# MTX_pic_piggyback_V12.net
KiCad netlist of a schematic drawn in EAGLE
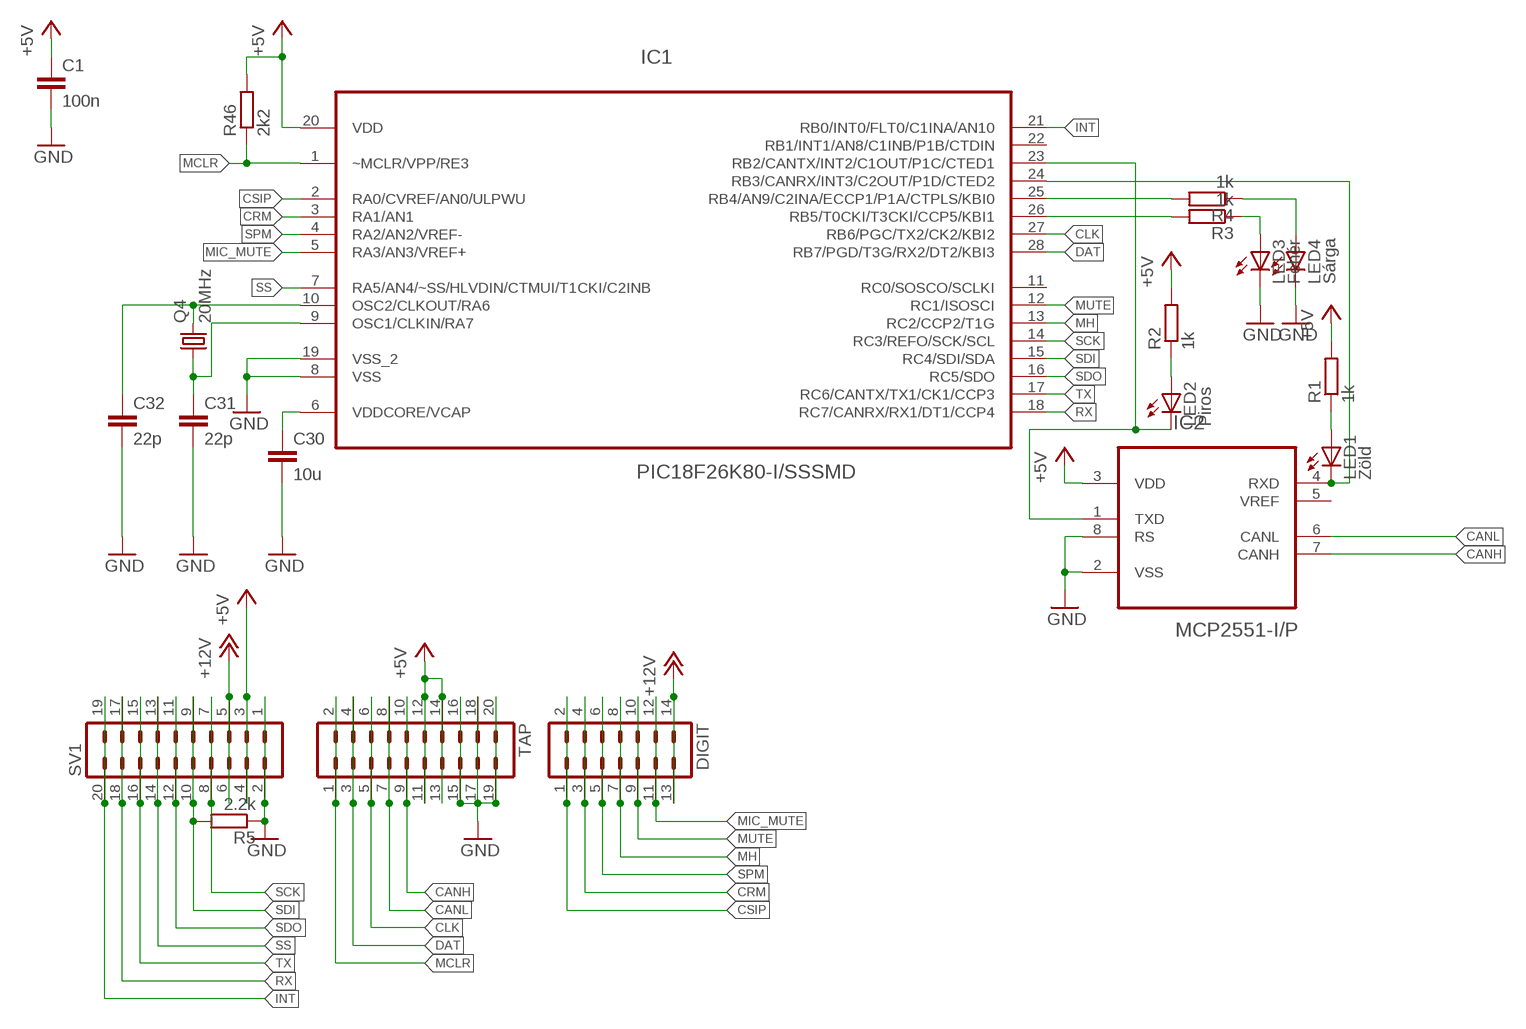
[diagram p0: schematic, sheet 1]

(export (version "E")
  (design (tool "Eeschema 10.0.6"))
  (components
    (comp (ref "C1")
      (value "100n")
      (footprint "eagle-import:C0805")
      (libsource (lib "eagle-import") (part "C-EUC0805"))
    )
    (comp (ref "C30")
      (value "10u")
      (footprint "eagle-import:C0805")
      (libsource (lib "eagle-import") (part "C-EUC0805"))
    )
    (comp (ref "C31")
      (value "22p")
      (footprint "eagle-import:C0805")
      (libsource (lib "eagle-import") (part "C-EUC0805"))
    )
    (comp (ref "C32")
      (value "22p")
      (footprint "eagle-import:C0805")
      (libsource (lib "eagle-import") (part "C-EUC0805"))
    )
    (comp (ref "DIGIT")
      (value "MA07-2")
      (footprint "eagle-import:MA07-2")
      (libsource (lib "eagle-import") (part "MA07-2"))
    )
    (comp (ref "IC1")
      (value "PIC18F26K80-I/SSSMD")
      (footprint "eagle-import:SOP65P780X200-28N")
      (libsource (lib "eagle-import") (part "PIC18F25K80-I/SSSMD"))
    )
    (comp (ref "IC2")
      (value "MCP2551-I/P")
      (footprint "eagle-import:DIP254P762X432-8")
      (libsource (lib "eagle-import") (part "MCP2551-I/P"))
    )
    (comp (ref "LED1")
      (value "Zöld")
      (footprint "eagle-import:CHIP-LED0805")
      (libsource (lib "eagle-import") (part "LEDCHIP-LED0805"))
    )
    (comp (ref "LED2")
      (value "Piros")
      (footprint "eagle-import:CHIP-LED0805")
      (libsource (lib "eagle-import") (part "LEDCHIP-LED0805"))
    )
    (comp (ref "LED3")
      (value "Fehér")
      (footprint "eagle-import:CHIP-LED0805")
      (libsource (lib "eagle-import") (part "LEDCHIP-LED0805"))
    )
    (comp (ref "LED4")
      (value "Sárga")
      (footprint "eagle-import:CHIP-LED0805")
      (libsource (lib "eagle-import") (part "LEDCHIP-LED0805"))
    )
    (comp (ref "Q4")
      (value "20MHz")
      (footprint "eagle-import:HC49UP")
      (libsource (lib "eagle-import") (part "CRYSTALHC49UP"))
    )
    (comp (ref "R1")
      (value "1k")
      (footprint "eagle-import:R0805")
      (libsource (lib "eagle-import") (part "R-EU_R0805"))
    )
    (comp (ref "R2")
      (value "1k")
      (footprint "eagle-import:R0805")
      (libsource (lib "eagle-import") (part "R-EU_R0805"))
    )
    (comp (ref "R3")
      (value "1k")
      (footprint "eagle-import:R0805")
      (libsource (lib "eagle-import") (part "R-EU_R0805"))
    )
    (comp (ref "R4")
      (value "1k")
      (footprint "eagle-import:R0805")
      (libsource (lib "eagle-import") (part "R-EU_R0805"))
    )
    (comp (ref "R5")
      (value "2.2k")
      (footprint "eagle-import:R0805")
      (libsource (lib "eagle-import") (part "R-EU_R0805"))
    )
    (comp (ref "R46")
      (value "2k2")
      (footprint "eagle-import:R0805")
      (libsource (lib "eagle-import") (part "R-EU_R0805"))
    )
    (comp (ref "SV1")
      (value "MA10-2")
      (footprint "eagle-import:MA10-2")
      (libsource (lib "eagle-import") (part "MA10-2"))
    )
    (comp (ref "TAP")
      (value "MA10-2")
      (footprint "eagle-import:MA10-2")
      (libsource (lib "eagle-import") (part "MA10-2"))
    )
  )
  (nets
    (net (code "1") (name "+5V") (class "Default")
      (node (ref "C1") (pin "1") (pinfunction "1_1") (pintype "passive"))
      (node (ref "IC1") (pin "20") (pinfunction "VDD_20") (pintype "power_in"))
      (node (ref "IC2") (pin "3") (pinfunction "VDD_3") (pintype "power_in"))
      (node (ref "R1") (pin "2") (pinfunction "2_2") (pintype "passive"))
      (node (ref "R2") (pin "2") (pinfunction "2_2") (pintype "passive"))
      (node (ref "R46") (pin "2") (pinfunction "2_2") (pintype "passive"))
      (node (ref "SV1") (pin "3") (pinfunction "3_3") (pintype "passive"))
      (node (ref "SV1") (pin "4") (pinfunction "4_4") (pintype "passive"))
      (node (ref "TAP") (pin "11") (pinfunction "11_11") (pintype "passive"))
      (node (ref "TAP") (pin "12") (pinfunction "12_12") (pintype "passive"))
      (node (ref "TAP") (pin "13") (pinfunction "13_13") (pintype "passive"))
      (node (ref "TAP") (pin "14") (pinfunction "14_14") (pintype "passive"))
    )
    (net (code "2") (name "+12V") (class "Default")
      (node (ref "DIGIT") (pin "13") (pinfunction "13_13") (pintype "passive"))
      (node (ref "DIGIT") (pin "14") (pinfunction "14_14") (pintype "passive"))
      (node (ref "SV1") (pin "5") (pinfunction "5_5") (pintype "passive"))
      (node (ref "SV1") (pin "6") (pinfunction "6_6") (pintype "passive"))
    )
    (net (code "3") (name "CANH") (class "Default")
      (node (ref "IC2") (pin "7") (pinfunction "CANH_7") (pintype "bidirectional"))
      (node (ref "TAP") (pin "10") (pinfunction "10_10") (pintype "passive"))
      (node (ref "TAP") (pin "9") (pinfunction "9_9") (pintype "passive"))
    )
    (net (code "4") (name "CANL") (class "Default")
      (node (ref "IC2") (pin "6") (pinfunction "CANL_6") (pintype "bidirectional"))
      (node (ref "TAP") (pin "7") (pinfunction "7_7") (pintype "passive"))
      (node (ref "TAP") (pin "8") (pinfunction "8_8") (pintype "passive"))
    )
    (net (code "5") (name "CLK") (class "Default")
      (node (ref "IC1") (pin "27") (pinfunction "RB6/PGC/TX2/CK2/KBI2_27") (pintype "bidirectional"))
      (node (ref "TAP") (pin "5") (pinfunction "5_5") (pintype "passive"))
      (node (ref "TAP") (pin "6") (pinfunction "6_6") (pintype "passive"))
    )
    (net (code "6") (name "CRM") (class "Default")
      (node (ref "DIGIT") (pin "3") (pinfunction "3_3") (pintype "passive"))
      (node (ref "DIGIT") (pin "4") (pinfunction "4_4") (pintype "passive"))
      (node (ref "IC1") (pin "3") (pinfunction "RA1/AN1_3") (pintype "bidirectional"))
    )
    (net (code "7") (name "CSIP") (class "Default")
      (node (ref "DIGIT") (pin "1") (pinfunction "1_1") (pintype "passive"))
      (node (ref "DIGIT") (pin "2") (pinfunction "2_2") (pintype "passive"))
      (node (ref "IC1") (pin "2") (pinfunction "RA0/CVREF/AN0/ULPWU_2") (pintype "bidirectional"))
    )
    (net (code "8") (name "DAT") (class "Default")
      (node (ref "IC1") (pin "28") (pinfunction "RB7/PGD/T3G/RX2/DT2/KBI3_28") (pintype "bidirectional"))
      (node (ref "TAP") (pin "3") (pinfunction "3_3") (pintype "passive"))
      (node (ref "TAP") (pin "4") (pinfunction "4_4") (pintype "passive"))
    )
    (net (code "9") (name "GND") (class "Default")
      (node (ref "C1") (pin "2") (pinfunction "2_2") (pintype "passive"))
      (node (ref "C30") (pin "2") (pinfunction "2_2") (pintype "passive"))
      (node (ref "C31") (pin "2") (pinfunction "2_2") (pintype "passive"))
      (node (ref "C32") (pin "2") (pinfunction "2_2") (pintype "passive"))
      (node (ref "IC1") (pin "19") (pinfunction "VSS_2_19") (pintype "power_in"))
      (node (ref "IC1") (pin "8") (pinfunction "VSS_8") (pintype "power_in"))
      (node (ref "IC2") (pin "2") (pinfunction "VSS_2") (pintype "power_in"))
      (node (ref "IC2") (pin "8") (pinfunction "RS_8") (pintype "input"))
      (node (ref "LED3") (pin "C") (pinfunction "C_C") (pintype "passive"))
      (node (ref "LED4") (pin "C") (pinfunction "C_C") (pintype "passive"))
      (node (ref "R5") (pin "1") (pinfunction "1_1") (pintype "passive"))
      (node (ref "SV1") (pin "1") (pinfunction "1_1") (pintype "passive"))
      (node (ref "SV1") (pin "2") (pinfunction "2_2") (pintype "passive"))
      (node (ref "TAP") (pin "15") (pinfunction "15_15") (pintype "passive"))
      (node (ref "TAP") (pin "16") (pinfunction "16_16") (pintype "passive"))
      (node (ref "TAP") (pin "17") (pinfunction "17_17") (pintype "passive"))
      (node (ref "TAP") (pin "18") (pinfunction "18_18") (pintype "passive"))
      (node (ref "TAP") (pin "19") (pinfunction "19_19") (pintype "passive"))
      (node (ref "TAP") (pin "20") (pinfunction "20_20") (pintype "passive"))
    )
    (net (code "10") (name "INT") (class "Default")
      (node (ref "IC1") (pin "21") (pinfunction "RB0/INT0/FLT0/C1INA/AN10_21") (pintype "bidirectional"))
      (node (ref "SV1") (pin "19") (pinfunction "19_19") (pintype "passive"))
      (node (ref "SV1") (pin "20") (pinfunction "20_20") (pintype "passive"))
    )
    (net (code "11") (name "MCLR") (class "Default")
      (node (ref "IC1") (pin "1") (pinfunction "~{MCLR/VPP/RE3}_1") (pintype "input"))
      (node (ref "R46") (pin "1") (pinfunction "1_1") (pintype "passive"))
      (node (ref "TAP") (pin "1") (pinfunction "1_1") (pintype "passive"))
      (node (ref "TAP") (pin "2") (pinfunction "2_2") (pintype "passive"))
    )
    (net (code "12") (name "MH") (class "Default")
      (node (ref "DIGIT") (pin "7") (pinfunction "7_7") (pintype "passive"))
      (node (ref "DIGIT") (pin "8") (pinfunction "8_8") (pintype "passive"))
      (node (ref "IC1") (pin "13") (pinfunction "RC2/CCP2/T1G_13") (pintype "bidirectional"))
    )
    (net (code "13") (name "MIC_MUTE") (class "Default")
      (node (ref "DIGIT") (pin "11") (pinfunction "11_11") (pintype "passive"))
      (node (ref "DIGIT") (pin "12") (pinfunction "12_12") (pintype "passive"))
      (node (ref "IC1") (pin "5") (pinfunction "RA3/AN3/VREF+_5") (pintype "bidirectional"))
    )
    (net (code "14") (name "MUTE") (class "Default")
      (node (ref "DIGIT") (pin "10") (pinfunction "10_10") (pintype "passive"))
      (node (ref "DIGIT") (pin "9") (pinfunction "9_9") (pintype "passive"))
      (node (ref "IC1") (pin "12") (pinfunction "RC1/ISOSCI_12") (pintype "bidirectional"))
    )
    (net (code "15") (name "Net-(IC1-OSC1{slash}CLKIN{slash}RA7)") (class "Default")
      (node (ref "C31") (pin "1") (pinfunction "1_1") (pintype "passive"))
      (node (ref "IC1") (pin "9") (pinfunction "OSC1/CLKIN/RA7_9") (pintype "bidirectional"))
      (node (ref "Q4") (pin "1") (pinfunction "1_1") (pintype "passive"))
    )
    (net (code "16") (name "Net-(IC1-OSC2{slash}CLKOUT{slash}RA6)") (class "Default")
      (node (ref "C32") (pin "1") (pinfunction "1_1") (pintype "passive"))
      (node (ref "IC1") (pin "10") (pinfunction "OSC2/CLKOUT/RA6_10") (pintype "bidirectional"))
      (node (ref "Q4") (pin "2") (pinfunction "2_2") (pintype "passive"))
    )
    (net (code "17") (name "Net-(IC1-RB2{slash}CANTX{slash}INT2{slash}C1OUT{slash}P1C{slash}CTED1)") (class "Default")
      (node (ref "IC1") (pin "23") (pinfunction "RB2/CANTX/INT2/C1OUT/P1C/CTED1_23") (pintype "bidirectional"))
      (node (ref "IC2") (pin "1") (pinfunction "TXD_1") (pintype "input"))
      (node (ref "LED2") (pin "C") (pinfunction "C_C") (pintype "passive"))
    )
    (net (code "18") (name "Net-(IC1-RB3{slash}CANRX{slash}INT3{slash}C2OUT{slash}P1D{slash}CTED2)") (class "Default")
      (node (ref "IC1") (pin "24") (pinfunction "RB3/CANRX/INT3/C2OUT/P1D/CTED2_24") (pintype "bidirectional"))
      (node (ref "IC2") (pin "4") (pinfunction "RXD_4") (pintype "output"))
      (node (ref "LED1") (pin "C") (pinfunction "C_C") (pintype "passive"))
    )
    (net (code "19") (name "Net-(IC1-RB4{slash}AN9{slash}C2INA{slash}ECCP1{slash}P1A{slash}CTPLS{slash}KBI0)") (class "Default")
      (node (ref "IC1") (pin "25") (pinfunction "RB4/AN9/C2INA/ECCP1/P1A/CTPLS/KBI0_25") (pintype "bidirectional"))
      (node (ref "R4") (pin "2") (pinfunction "2_2") (pintype "passive"))
    )
    (net (code "20") (name "Net-(IC1-RB5{slash}T0CKI{slash}T3CKI{slash}CCP5{slash}KBI1)") (class "Default")
      (node (ref "IC1") (pin "26") (pinfunction "RB5/T0CKI/T3CKI/CCP5/KBI1_26") (pintype "bidirectional"))
      (node (ref "R3") (pin "2") (pinfunction "2_2") (pintype "passive"))
    )
    (net (code "21") (name "Net-(IC1-VDDCORE{slash}VCAP)") (class "Default")
      (node (ref "C30") (pin "1") (pinfunction "1_1") (pintype "passive"))
      (node (ref "IC1") (pin "6") (pinfunction "VDDCORE/VCAP_6") (pintype "bidirectional"))
    )
    (net (code "22") (name "Net-(LED1-PadA)") (class "Default")
      (node (ref "LED1") (pin "A") (pinfunction "A_A") (pintype "passive"))
      (node (ref "R1") (pin "1") (pinfunction "1_1") (pintype "passive"))
    )
    (net (code "23") (name "Net-(LED2-PadA)") (class "Default")
      (node (ref "LED2") (pin "A") (pinfunction "A_A") (pintype "passive"))
      (node (ref "R2") (pin "1") (pinfunction "1_1") (pintype "passive"))
    )
    (net (code "24") (name "Net-(LED3-PadA)") (class "Default")
      (node (ref "LED3") (pin "A") (pinfunction "A_A") (pintype "passive"))
      (node (ref "R3") (pin "1") (pinfunction "1_1") (pintype "passive"))
    )
    (net (code "25") (name "Net-(LED4-PadA)") (class "Default")
      (node (ref "LED4") (pin "A") (pinfunction "A_A") (pintype "passive"))
      (node (ref "R4") (pin "1") (pinfunction "1_1") (pintype "passive"))
    )
    (net (code "26") (name "RX") (class "Default")
      (node (ref "IC1") (pin "18") (pinfunction "RC7/CANRX/RX1/DT1/CCP4_18") (pintype "bidirectional"))
      (node (ref "SV1") (pin "17") (pinfunction "17_17") (pintype "passive"))
      (node (ref "SV1") (pin "18") (pinfunction "18_18") (pintype "passive"))
    )
    (net (code "27") (name "SCK") (class "Default")
      (node (ref "IC1") (pin "14") (pinfunction "RC3/REFO/SCK/SCL_14") (pintype "bidirectional"))
      (node (ref "SV1") (pin "7") (pinfunction "7_7") (pintype "passive"))
      (node (ref "SV1") (pin "8") (pinfunction "8_8") (pintype "passive"))
    )
    (net (code "28") (name "SDI") (class "Default")
      (node (ref "IC1") (pin "15") (pinfunction "RC4/SDI/SDA_15") (pintype "bidirectional"))
      (node (ref "R5") (pin "2") (pinfunction "2_2") (pintype "passive"))
      (node (ref "SV1") (pin "10") (pinfunction "10_10") (pintype "passive"))
      (node (ref "SV1") (pin "9") (pinfunction "9_9") (pintype "passive"))
    )
    (net (code "29") (name "SDO") (class "Default")
      (node (ref "IC1") (pin "16") (pinfunction "RC5/SDO_16") (pintype "bidirectional"))
      (node (ref "SV1") (pin "11") (pinfunction "11_11") (pintype "passive"))
      (node (ref "SV1") (pin "12") (pinfunction "12_12") (pintype "passive"))
    )
    (net (code "30") (name "SPM") (class "Default")
      (node (ref "DIGIT") (pin "5") (pinfunction "5_5") (pintype "passive"))
      (node (ref "DIGIT") (pin "6") (pinfunction "6_6") (pintype "passive"))
      (node (ref "IC1") (pin "4") (pinfunction "RA2/AN2/VREF-_4") (pintype "bidirectional"))
    )
    (net (code "31") (name "SS") (class "Default")
      (node (ref "IC1") (pin "7") (pinfunction "RA5/AN4/~{SS/HLVDIN/CTMUI/T1CKI/C2INB}_7") (pintype "bidirectional"))
      (node (ref "SV1") (pin "13") (pinfunction "13_13") (pintype "passive"))
      (node (ref "SV1") (pin "14") (pinfunction "14_14") (pintype "passive"))
    )
    (net (code "32") (name "TX") (class "Default")
      (node (ref "IC1") (pin "17") (pinfunction "RC6/CANTX/TX1/CK1/CCP3_17") (pintype "bidirectional"))
      (node (ref "SV1") (pin "15") (pinfunction "15_15") (pintype "passive"))
      (node (ref "SV1") (pin "16") (pinfunction "16_16") (pintype "passive"))
    )
    (net (code "33") (name "unconnected-(IC1-RB1{slash}INT1{slash}AN8{slash}C1INB{slash}P1B{slash}CTDIN-Pad22)") (class "Default")
      (node (ref "IC1") (pin "22") (pinfunction "RB1/INT1/AN8/C1INB/P1B/CTDIN_22") (pintype "bidirectional"))
    )
    (net (code "34") (name "unconnected-(IC1-RC0{slash}SOSCO{slash}SCLKI-Pad11)") (class "Default")
      (node (ref "IC1") (pin "11") (pinfunction "RC0/SOSCO/SCLKI_11") (pintype "bidirectional"))
    )
    (net (code "35") (name "unconnected-(IC2-VREF-Pad5)") (class "Default")
      (node (ref "IC2") (pin "5") (pinfunction "VREF_5") (pintype "output"))
    )
  )
)
